# wiggle_jig.net
KiCad netlist of a schematic drawn in EAGLE
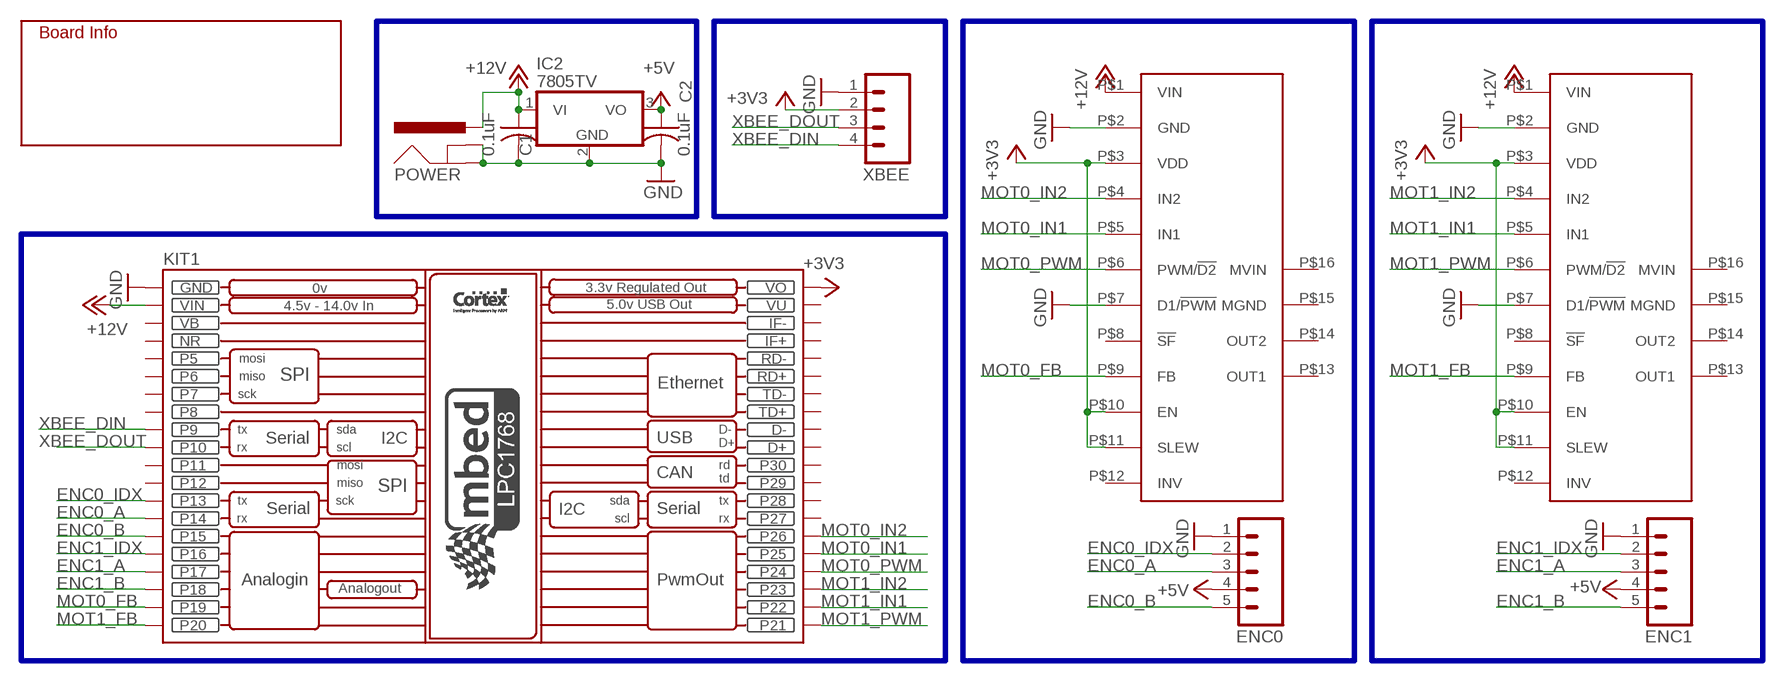
[diagram p0: schematic, sheet 1]

(export (version "E")
  (design (tool "Eeschema 10.0.6"))
  (components
    (comp (ref "C1")
      (value "0.1uF")
      (footprint "eagle-import:C025-025X050")
      (libsource (lib "eagle-import") (part "C-US025-025X050"))
    )
    (comp (ref "C2")
      (value "0.1uF")
      (footprint "eagle-import:C025-025X050")
      (libsource (lib "eagle-import") (part "C-US025-025X050"))
    )
    (comp (ref "ENC0")
      (value "M05LOCK")
      (footprint "eagle-import:1X05_LOCK")
      (libsource (lib "eagle-import") (part "M05LOCK"))
    )
    (comp (ref "ENC1")
      (value "M05LOCK")
      (footprint "eagle-import:1X05_LOCK")
      (libsource (lib "eagle-import") (part "M05LOCK"))
    )
    (comp (ref "IC2")
      (value "7805TV")
      (footprint "eagle-import:TO220V")
      (libsource (lib "eagle-import") (part "78TV05"))
    )
    (comp (ref "KIT1")
      (value "MBED_NXP_LPC1768")
      (footprint "eagle-import:MBED-KIT")
      (libsource (lib "eagle-import") (part "MBED_NXP_LPC1768"))
    )
    (comp (ref "MOT0")
      (value "MC33926_CARRIER")
      (footprint "eagle-import:MC33926_CARRIER")
      (libsource (lib "eagle-import") (part "MC33926_CARRIER"))
    )
    (comp (ref "MOT1")
      (value "MC33926_CARRIER")
      (footprint "eagle-import:MC33926_CARRIER")
      (libsource (lib "eagle-import") (part "MC33926_CARRIER"))
    )
    (comp (ref "POWER")
      (value "POWER_JACKPTH_LOCK")
      (footprint "eagle-import:POWER_JACK_PTH_LOCK")
      (libsource (lib "eagle-import") (part "POWER_JACKPTH_LOCK"))
    )
    (comp (ref "U$4")
      (value "INFO")
      (footprint "eagle-import:INFO")
      (fields
        (field (name "AUTHOR") "A. Buchan")
        (field (name "DATE") "Oct. 19, 2016")
        (field (name "DESIGN") "WiggleJig")
        (field (name "ORGANIZATION") "Biomimetic Millisystems Lab")
        (field (name "REVISION") "r0.0")
      )
      (libsource (lib "eagle-import") (part "INFO"))
    )
    (comp (ref "XBEE")
      (value "M04LOCK")
      (footprint "eagle-import:1X04_LOCK")
      (libsource (lib "eagle-import") (part "M04LOCK"))
    )
  )
  (nets
    (net (code "1") (name "+3V3") (class "Default")
      (node (ref "KIT1") (pin "VOUT") (pinfunction "VO_VOUT") (pintype "power_in"))
      (node (ref "MOT0") (pin "P$10") (pinfunction "EN_P$10") (pintype "bidirectional"))
      (node (ref "MOT0") (pin "P$11") (pinfunction "SLEW_P$11") (pintype "bidirectional"))
      (node (ref "MOT0") (pin "P$3") (pinfunction "VDD_P$3") (pintype "bidirectional"))
      (node (ref "MOT1") (pin "P$10") (pinfunction "EN_P$10") (pintype "bidirectional"))
      (node (ref "MOT1") (pin "P$11") (pinfunction "SLEW_P$11") (pintype "bidirectional"))
      (node (ref "MOT1") (pin "P$3") (pinfunction "VDD_P$3") (pintype "bidirectional"))
      (node (ref "XBEE") (pin "2") (pinfunction "2_2") (pintype "passive"))
    )
    (net (code "2") (name "+5V") (class "Default")
      (node (ref "C2") (pin "1") (pinfunction "1_1") (pintype "passive"))
      (node (ref "ENC0") (pin "4") (pinfunction "4_4") (pintype "passive"))
      (node (ref "ENC1") (pin "4") (pinfunction "4_4") (pintype "passive"))
      (node (ref "IC2") (pin "3") (pinfunction "VO_3") (pintype "passive"))
    )
    (net (code "3") (name "+12V") (class "Default")
      (node (ref "C1") (pin "1") (pinfunction "1_1") (pintype "passive"))
      (node (ref "IC2") (pin "1") (pinfunction "VI_1") (pintype "input"))
      (node (ref "KIT1") (pin "VIN") (pinfunction "VIN_VIN") (pintype "power_in"))
      (node (ref "MOT0") (pin "P$1") (pinfunction "VIN_P$1") (pintype "bidirectional"))
      (node (ref "MOT1") (pin "P$1") (pinfunction "VIN_P$1") (pintype "bidirectional"))
      (node (ref "POWER") (pin "PWR") (pinfunction "PWR_PWR") (pintype "bidirectional"))
    )
    (net (code "4") (name "/ENC0_A") (class "Default")
      (node (ref "ENC0") (pin "3") (pinfunction "3_3") (pintype "passive"))
      (node (ref "KIT1") (pin "P$14") (pinfunction "P14_P$14") (pintype "bidirectional"))
    )
    (net (code "5") (name "/ENC0_B") (class "Default")
      (node (ref "ENC0") (pin "5") (pinfunction "5_5") (pintype "passive"))
      (node (ref "KIT1") (pin "P$15") (pinfunction "P15_P$15") (pintype "bidirectional"))
    )
    (net (code "6") (name "/ENC0_IDX") (class "Default")
      (node (ref "ENC0") (pin "2") (pinfunction "2_2") (pintype "passive"))
      (node (ref "KIT1") (pin "P$13") (pinfunction "P13_P$13") (pintype "bidirectional"))
    )
    (net (code "7") (name "/ENC1_A") (class "Default")
      (node (ref "ENC1") (pin "3") (pinfunction "3_3") (pintype "passive"))
      (node (ref "KIT1") (pin "P$17") (pinfunction "P17_P$17") (pintype "bidirectional"))
    )
    (net (code "8") (name "/ENC1_B") (class "Default")
      (node (ref "ENC1") (pin "5") (pinfunction "5_5") (pintype "passive"))
      (node (ref "KIT1") (pin "P$18") (pinfunction "P18_P$18") (pintype "bidirectional"))
    )
    (net (code "9") (name "/ENC1_IDX") (class "Default")
      (node (ref "ENC1") (pin "2") (pinfunction "2_2") (pintype "passive"))
      (node (ref "KIT1") (pin "P$16") (pinfunction "P16_P$16") (pintype "bidirectional"))
    )
    (net (code "10") (name "/MOT0_FB") (class "Default")
      (node (ref "KIT1") (pin "P$19") (pinfunction "P19_P$19") (pintype "bidirectional"))
      (node (ref "MOT0") (pin "P$9") (pinfunction "FB_P$9") (pintype "bidirectional"))
    )
    (net (code "11") (name "/MOT0_IN1") (class "Default")
      (node (ref "KIT1") (pin "P$25") (pinfunction "P25_P$25") (pintype "bidirectional"))
      (node (ref "MOT0") (pin "P$5") (pinfunction "IN1_P$5") (pintype "bidirectional"))
    )
    (net (code "12") (name "/MOT0_IN2") (class "Default")
      (node (ref "KIT1") (pin "P$26") (pinfunction "P26_P$26") (pintype "bidirectional"))
      (node (ref "MOT0") (pin "P$4") (pinfunction "IN2_P$4") (pintype "bidirectional"))
    )
    (net (code "13") (name "/MOT0_PWM") (class "Default")
      (node (ref "KIT1") (pin "P$24") (pinfunction "P24_P$24") (pintype "bidirectional"))
      (node (ref "MOT0") (pin "P$6") (pinfunction "PWM/~{D2}_P$6") (pintype "bidirectional"))
    )
    (net (code "14") (name "/MOT1_FB") (class "Default")
      (node (ref "KIT1") (pin "P$20") (pinfunction "P20_P$20") (pintype "bidirectional"))
      (node (ref "MOT1") (pin "P$9") (pinfunction "FB_P$9") (pintype "bidirectional"))
    )
    (net (code "15") (name "/MOT1_IN1") (class "Default")
      (node (ref "KIT1") (pin "P$22") (pinfunction "P22_P$22") (pintype "bidirectional"))
      (node (ref "MOT1") (pin "P$5") (pinfunction "IN1_P$5") (pintype "bidirectional"))
    )
    (net (code "16") (name "/MOT1_IN2") (class "Default")
      (node (ref "KIT1") (pin "P$23") (pinfunction "P23_P$23") (pintype "bidirectional"))
      (node (ref "MOT1") (pin "P$4") (pinfunction "IN2_P$4") (pintype "bidirectional"))
    )
    (net (code "17") (name "/MOT1_PWM") (class "Default")
      (node (ref "KIT1") (pin "P$21") (pinfunction "P21_P$21") (pintype "bidirectional"))
      (node (ref "MOT1") (pin "P$6") (pinfunction "PWM/~{D2}_P$6") (pintype "bidirectional"))
    )
    (net (code "18") (name "/NR") (class "Default")
      (node (ref "KIT1") (pin "NR") (pinfunction "NR_NR") (pintype "power_in"))
    )
    (net (code "19") (name "/VB") (class "Default")
      (node (ref "KIT1") (pin "VB") (pinfunction "VB_VB") (pintype "power_in"))
    )
    (net (code "20") (name "/VU") (class "Default")
      (node (ref "KIT1") (pin "VU") (pinfunction "VU_VU") (pintype "power_in"))
    )
    (net (code "21") (name "/XBEE_DIN") (class "Default")
      (node (ref "KIT1") (pin "P$9") (pinfunction "P9_P$9") (pintype "bidirectional"))
      (node (ref "XBEE") (pin "4") (pinfunction "4_4") (pintype "passive"))
    )
    (net (code "22") (name "/XBEE_DOUT") (class "Default")
      (node (ref "KIT1") (pin "P$10") (pinfunction "P10_P$10") (pintype "bidirectional"))
      (node (ref "XBEE") (pin "3") (pinfunction "3_3") (pintype "passive"))
    )
    (net (code "23") (name "GND") (class "Default")
      (node (ref "C1") (pin "2") (pinfunction "2_2") (pintype "passive"))
      (node (ref "C2") (pin "2") (pinfunction "2_2") (pintype "passive"))
      (node (ref "ENC0") (pin "1") (pinfunction "1_1") (pintype "passive"))
      (node (ref "ENC1") (pin "1") (pinfunction "1_1") (pintype "passive"))
      (node (ref "IC2") (pin "2") (pinfunction "GND_2") (pintype "passive"))
      (node (ref "KIT1") (pin "GND") (pinfunction "GND_GND") (pintype "power_in"))
      (node (ref "MOT0") (pin "P$2") (pinfunction "GND_P$2") (pintype "bidirectional"))
      (node (ref "MOT0") (pin "P$7") (pinfunction "D1/~{PWM}_P$7") (pintype "bidirectional"))
      (node (ref "MOT1") (pin "P$2") (pinfunction "GND_P$2") (pintype "bidirectional"))
      (node (ref "MOT1") (pin "P$7") (pinfunction "D1/~{PWM}_P$7") (pintype "bidirectional"))
      (node (ref "POWER") (pin "GND") (pinfunction "GND_GND") (pintype "bidirectional"))
      (node (ref "POWER") (pin "GNDBREAK") (pinfunction "GNDBREAK_GNDBREAK") (pintype "bidirectional"))
      (node (ref "XBEE") (pin "1") (pinfunction "1_1") (pintype "passive"))
    )
    (net (code "24") (name "unconnected-(KIT1-P5-PadP$5)") (class "Default")
      (node (ref "KIT1") (pin "P$5") (pinfunction "P5_P$5") (pintype "bidirectional"))
    )
    (net (code "25") (name "unconnected-(KIT1-P6-PadP$6)") (class "Default")
      (node (ref "KIT1") (pin "P$6") (pinfunction "P6_P$6") (pintype "bidirectional"))
    )
    (net (code "26") (name "unconnected-(KIT1-P7-PadP$7)") (class "Default")
      (node (ref "KIT1") (pin "P$7") (pinfunction "P7_P$7") (pintype "bidirectional"))
    )
    (net (code "27") (name "unconnected-(KIT1-P8-PadP$8)") (class "Default")
      (node (ref "KIT1") (pin "P$8") (pinfunction "P8_P$8") (pintype "bidirectional"))
    )
    (net (code "28") (name "unconnected-(KIT1-P11-PadP$11)") (class "Default")
      (node (ref "KIT1") (pin "P$11") (pinfunction "P11_P$11") (pintype "bidirectional"))
    )
    (net (code "29") (name "unconnected-(KIT1-P12-PadP$12)") (class "Default")
      (node (ref "KIT1") (pin "P$12") (pinfunction "P12_P$12") (pintype "bidirectional"))
    )
    (net (code "30") (name "unconnected-(KIT1-P27-PadP$27)") (class "Default")
      (node (ref "KIT1") (pin "P$27") (pinfunction "P27_P$27") (pintype "bidirectional"))
    )
    (net (code "31") (name "unconnected-(KIT1-P28-PadP$28)") (class "Default")
      (node (ref "KIT1") (pin "P$28") (pinfunction "P28_P$28") (pintype "bidirectional"))
    )
    (net (code "32") (name "unconnected-(KIT1-P29-PadP$29)") (class "Default")
      (node (ref "KIT1") (pin "P$29") (pinfunction "P29_P$29") (pintype "bidirectional"))
    )
    (net (code "33") (name "unconnected-(KIT1-P30-PadP$30)") (class "Default")
      (node (ref "KIT1") (pin "P$30") (pinfunction "P30_P$30") (pintype "bidirectional"))
    )
    (net (code "34") (name "unconnected-(KIT1-PadD+)") (class "Default")
      (node (ref "KIT1") (pin "D+") (pinfunction "D+_D+") (pintype "bidirectional"))
    )
    (net (code "35") (name "unconnected-(KIT1-PadD-)") (class "Default")
      (node (ref "KIT1") (pin "D-") (pinfunction "D-_D-") (pintype "bidirectional"))
    )
    (net (code "36") (name "unconnected-(KIT1-PadIF+)") (class "Default")
      (node (ref "KIT1") (pin "IF+") (pinfunction "IF+_IF+") (pintype "bidirectional"))
    )
    (net (code "37") (name "unconnected-(KIT1-PadIF-)") (class "Default")
      (node (ref "KIT1") (pin "IF-") (pinfunction "IF-_IF-") (pintype "bidirectional"))
    )
    (net (code "38") (name "unconnected-(KIT1-PadRD+)") (class "Default")
      (node (ref "KIT1") (pin "RD+") (pinfunction "RD+_RD+") (pintype "bidirectional"))
    )
    (net (code "39") (name "unconnected-(KIT1-PadRD-)") (class "Default")
      (node (ref "KIT1") (pin "RD-") (pinfunction "RD-_RD-") (pintype "bidirectional"))
    )
    (net (code "40") (name "unconnected-(KIT1-PadTD+)") (class "Default")
      (node (ref "KIT1") (pin "TD+") (pinfunction "TD+_TD+") (pintype "bidirectional"))
    )
    (net (code "41") (name "unconnected-(KIT1-PadTD-)") (class "Default")
      (node (ref "KIT1") (pin "TD-") (pinfunction "TD-_TD-") (pintype "bidirectional"))
    )
    (net (code "42") (name "unconnected-(MOT0-INV-PadP$12)") (class "Default")
      (node (ref "MOT0") (pin "P$12") (pinfunction "INV_P$12") (pintype "bidirectional"))
    )
    (net (code "43") (name "unconnected-(MOT0-MGND-PadP$15)") (class "Default")
      (node (ref "MOT0") (pin "P$15") (pinfunction "MGND_P$15") (pintype "bidirectional"))
    )
    (net (code "44") (name "unconnected-(MOT0-MVIN-PadP$16)") (class "Default")
      (node (ref "MOT0") (pin "P$16") (pinfunction "MVIN_P$16") (pintype "bidirectional"))
    )
    (net (code "45") (name "unconnected-(MOT0-OUT1-PadP$13)") (class "Default")
      (node (ref "MOT0") (pin "P$13") (pinfunction "OUT1_P$13") (pintype "bidirectional"))
    )
    (net (code "46") (name "unconnected-(MOT0-OUT2-PadP$14)") (class "Default")
      (node (ref "MOT0") (pin "P$14") (pinfunction "OUT2_P$14") (pintype "bidirectional"))
    )
    (net (code "47") (name "unconnected-(MOT0-~{SF}-PadP$8)") (class "Default")
      (node (ref "MOT0") (pin "P$8") (pinfunction "~{SF}_P$8") (pintype "bidirectional"))
    )
    (net (code "48") (name "unconnected-(MOT1-INV-PadP$12)") (class "Default")
      (node (ref "MOT1") (pin "P$12") (pinfunction "INV_P$12") (pintype "bidirectional"))
    )
    (net (code "49") (name "unconnected-(MOT1-MGND-PadP$15)") (class "Default")
      (node (ref "MOT1") (pin "P$15") (pinfunction "MGND_P$15") (pintype "bidirectional"))
    )
    (net (code "50") (name "unconnected-(MOT1-MVIN-PadP$16)") (class "Default")
      (node (ref "MOT1") (pin "P$16") (pinfunction "MVIN_P$16") (pintype "bidirectional"))
    )
    (net (code "51") (name "unconnected-(MOT1-OUT1-PadP$13)") (class "Default")
      (node (ref "MOT1") (pin "P$13") (pinfunction "OUT1_P$13") (pintype "bidirectional"))
    )
    (net (code "52") (name "unconnected-(MOT1-OUT2-PadP$14)") (class "Default")
      (node (ref "MOT1") (pin "P$14") (pinfunction "OUT2_P$14") (pintype "bidirectional"))
    )
    (net (code "53") (name "unconnected-(MOT1-~{SF}-PadP$8)") (class "Default")
      (node (ref "MOT1") (pin "P$8") (pinfunction "~{SF}_P$8") (pintype "bidirectional"))
    )
  )
)
